# Placa_ATMEL_2019_v2.net
KiCad netlist of a schematic drawn in EAGLE
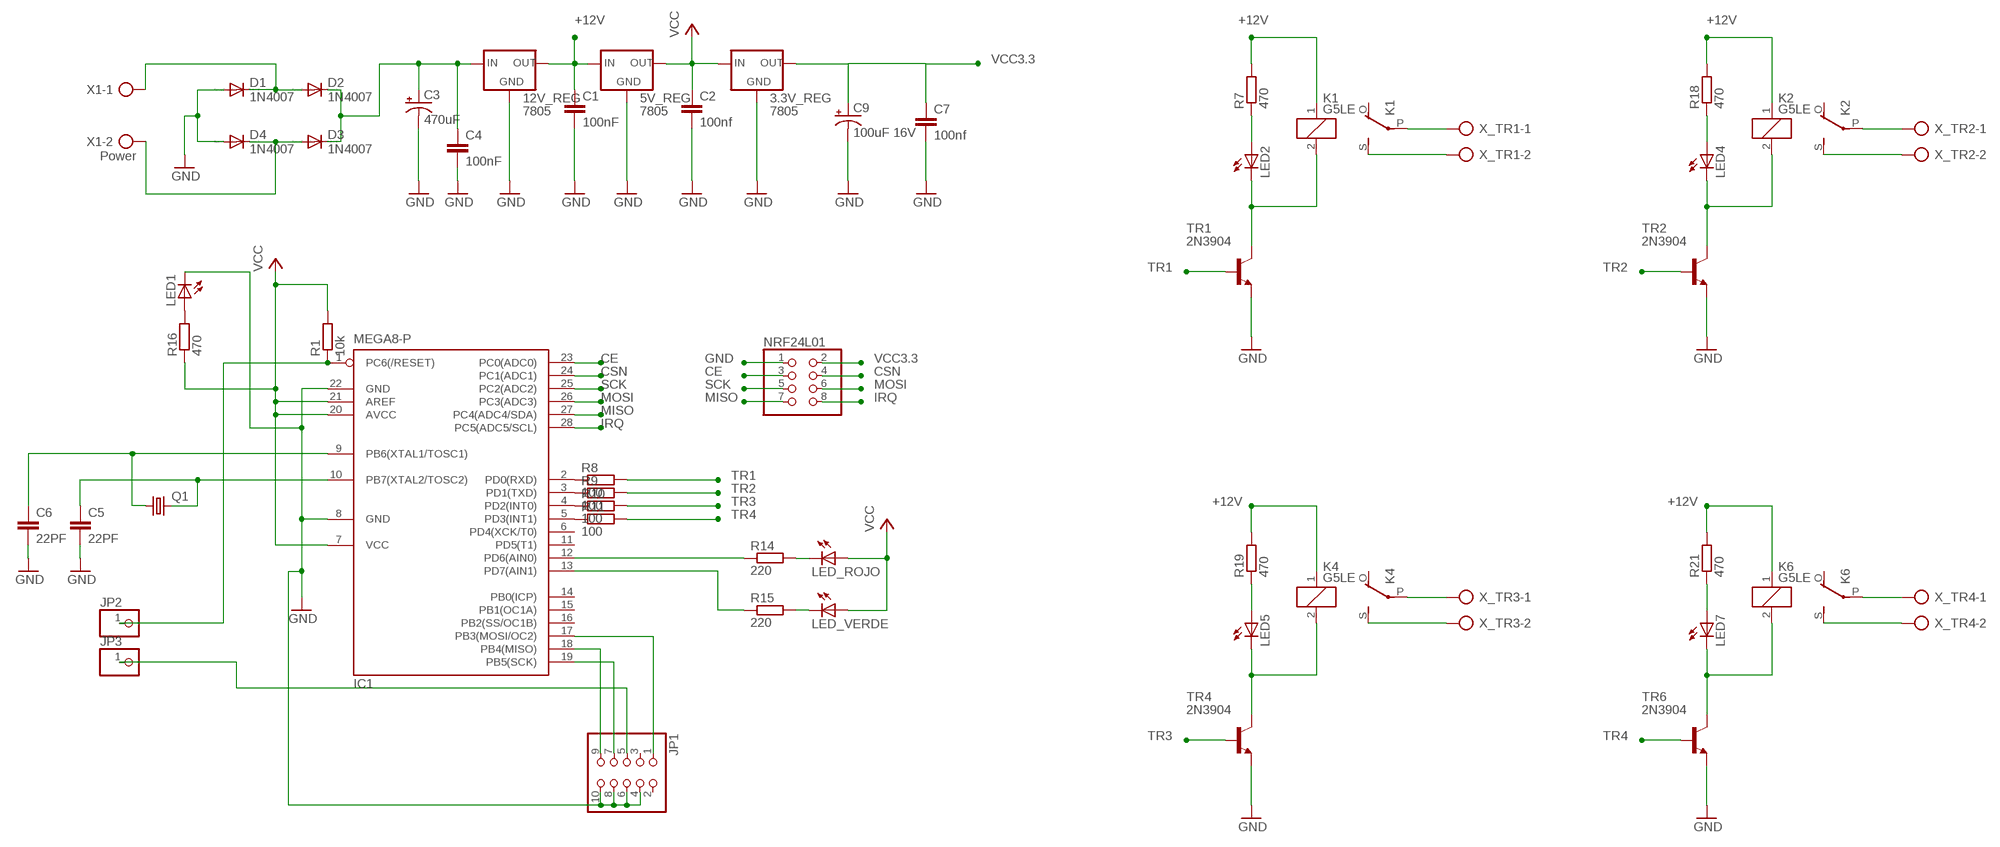
[diagram p0: schematic, sheet 1]

(export (version "E")
  (design (tool "Eeschema 10.0.6"))
  (components
    (comp (ref "3.3V_REG")
      (value "7805")
      (footprint "eagle-import:78XXL")
      (libsource (lib "eagle-import") (part "78XXL"))
    )
    (comp (ref "5V_REG")
      (value "7805")
      (footprint "eagle-import:78XXL")
      (libsource (lib "eagle-import") (part "78XXL"))
    )
    (comp (ref "12V_REG")
      (value "7805")
      (footprint "eagle-import:78XXL")
      (libsource (lib "eagle-import") (part "78XXL"))
    )
    (comp (ref "C1")
      (value "100nF")
      (footprint "eagle-import:C050-025X075")
      (libsource (lib "eagle-import") (part "C-EU050-025X075"))
    )
    (comp (ref "C2")
      (value "100nf")
      (footprint "eagle-import:C050-025X075")
      (libsource (lib "eagle-import") (part "C-EU050-025X075"))
    )
    (comp (ref "C3")
      (value "470uF")
      (footprint "eagle-import:E7,5-16")
      (libsource (lib "eagle-import") (part "CPOL-USE7.5-16"))
    )
    (comp (ref "C4")
      (value "100nF")
      (footprint "eagle-import:C050-025X075")
      (libsource (lib "eagle-import") (part "C-EU050-025X075"))
    )
    (comp (ref "C5")
      (value "22PF")
      (footprint "eagle-import:C050-024X044")
      (libsource (lib "eagle-import") (part "C-EU050-024X044"))
    )
    (comp (ref "C6")
      (value "22PF")
      (footprint "eagle-import:C050-024X044")
      (libsource (lib "eagle-import") (part "C-EU050-024X044"))
    )
    (comp (ref "C7")
      (value "100nf")
      (footprint "eagle-import:C050-025X075")
      (libsource (lib "eagle-import") (part "C-EU050-025X075"))
    )
    (comp (ref "C9")
      (value "100uF 16V")
      (footprint "eagle-import:E2,5-7")
      (libsource (lib "eagle-import") (part "CPOL-USE2.5-7"))
    )
    (comp (ref "D1")
      (value "1N4007")
      (footprint "eagle-import:DO41-10")
      (libsource (lib "eagle-import") (part "1N4004"))
    )
    (comp (ref "D2")
      (value "1N4007")
      (footprint "eagle-import:DO41-10")
      (libsource (lib "eagle-import") (part "1N4004"))
    )
    (comp (ref "D3")
      (value "1N4007")
      (footprint "eagle-import:DO41-10")
      (libsource (lib "eagle-import") (part "1N4004"))
    )
    (comp (ref "D4")
      (value "1N4007")
      (footprint "eagle-import:DO41-10")
      (libsource (lib "eagle-import") (part "1N4004"))
    )
    (comp (ref "IC1")
      (value "MEGA8-P")
      (footprint "eagle-import:DIL28-3")
      (libsource (lib "eagle-import") (part "MEGA8-P"))
    )
    (comp (ref "JP1")
      (value "PINHD-2X5")
      (footprint "eagle-import:2X05")
      (libsource (lib "eagle-import") (part "PINHD-2X5"))
    )
    (comp (ref "JP2")
      (value "PINHD-1X1")
      (footprint "eagle-import:1X01")
      (libsource (lib "eagle-import") (part "PINHD-1X1"))
    )
    (comp (ref "JP3")
      (value "PINHD-1X1")
      (footprint "eagle-import:1X01")
      (libsource (lib "eagle-import") (part "PINHD-1X1"))
    )
    (comp (ref "K1")
      (value "G5LE")
      (footprint "eagle-import:G5LE")
      (libsource (lib "eagle-import") (part "G5LE"))
    )
    (comp (ref "K2")
      (value "G5LE")
      (footprint "eagle-import:G5LE")
      (libsource (lib "eagle-import") (part "G5LE"))
    )
    (comp (ref "K4")
      (value "G5LE")
      (footprint "eagle-import:G5LE")
      (libsource (lib "eagle-import") (part "G5LE"))
    )
    (comp (ref "K6")
      (value "G5LE")
      (footprint "eagle-import:G5LE")
      (libsource (lib "eagle-import") (part "G5LE"))
    )
    (comp (ref "LED1")
      (value "LED5MM")
      (footprint "eagle-import:LED5MM")
      (libsource (lib "eagle-import") (part "LED5MM"))
    )
    (comp (ref "LED2")
      (value "LED5MM")
      (footprint "eagle-import:LED5MM")
      (libsource (lib "eagle-import") (part "LED5MM"))
    )
    (comp (ref "LED4")
      (value "LED5MM")
      (footprint "eagle-import:LED5MM")
      (libsource (lib "eagle-import") (part "LED5MM"))
    )
    (comp (ref "LED5")
      (value "LED5MM")
      (footprint "eagle-import:LED5MM")
      (libsource (lib "eagle-import") (part "LED5MM"))
    )
    (comp (ref "LED7")
      (value "LED5MM")
      (footprint "eagle-import:LED5MM")
      (libsource (lib "eagle-import") (part "LED5MM"))
    )
    (comp (ref "LED_ROJO")
      (value "LED5MM")
      (footprint "eagle-import:LED5MM")
      (libsource (lib "eagle-import") (part "LED5MM"))
    )
    (comp (ref "LED_VERDE")
      (value "LED5MM")
      (footprint "eagle-import:LED5MM")
      (libsource (lib "eagle-import") (part "LED5MM"))
    )
    (comp (ref "NRF24L01")
      (value "PINHD-2X4")
      (footprint "eagle-import:2X04")
      (libsource (lib "eagle-import") (part "PINHD-2X4"))
    )
    (comp (ref "Q1")
      (value "CRYSTALHC49S")
      (footprint "eagle-import:HC49_S")
      (libsource (lib "eagle-import") (part "CRYSTALHC49S"))
    )
    (comp (ref "R1")
      (value "10k")
      (footprint "eagle-import:0207_10")
      (libsource (lib "eagle-import") (part "R-EU_0207/10"))
    )
    (comp (ref "R7")
      (value "470")
      (footprint "eagle-import:0309_10")
      (libsource (lib "eagle-import") (part "R-EU_0309/10"))
    )
    (comp (ref "R8")
      (value "100")
      (footprint "eagle-import:0207_10")
      (libsource (lib "eagle-import") (part "R-EU_0207/10"))
    )
    (comp (ref "R9")
      (value "100")
      (footprint "eagle-import:0207_10")
      (libsource (lib "eagle-import") (part "R-EU_0207/10"))
    )
    (comp (ref "R10")
      (value "100")
      (footprint "eagle-import:0207_15")
      (libsource (lib "eagle-import") (part "R-EU_0207/15"))
    )
    (comp (ref "R11")
      (value "100")
      (footprint "eagle-import:0207_10")
      (libsource (lib "eagle-import") (part "R-EU_0207/10"))
    )
    (comp (ref "R14")
      (value "220")
      (footprint "eagle-import:0207_10")
      (libsource (lib "eagle-import") (part "R-EU_0207/10"))
    )
    (comp (ref "R15")
      (value "220")
      (footprint "eagle-import:0207_10")
      (libsource (lib "eagle-import") (part "R-EU_0207/10"))
    )
    (comp (ref "R16")
      (value "470")
      (footprint "eagle-import:0309_10")
      (libsource (lib "eagle-import") (part "R-EU_0309/10"))
    )
    (comp (ref "R18")
      (value "470")
      (footprint "eagle-import:0309_10")
      (libsource (lib "eagle-import") (part "R-EU_0309/10"))
    )
    (comp (ref "R19")
      (value "470")
      (footprint "eagle-import:0309_10")
      (libsource (lib "eagle-import") (part "R-EU_0309/10"))
    )
    (comp (ref "R21")
      (value "470")
      (footprint "eagle-import:0309_10")
      (libsource (lib "eagle-import") (part "R-EU_0309/10"))
    )
    (comp (ref "TR1")
      (value "2N3904")
      (footprint "eagle-import:TO92")
      (libsource (lib "eagle-import") (part "2N3904"))
    )
    (comp (ref "TR2")
      (value "2N3904")
      (footprint "eagle-import:TO92")
      (libsource (lib "eagle-import") (part "2N3904"))
    )
    (comp (ref "TR4")
      (value "2N3904")
      (footprint "eagle-import:TO92")
      (libsource (lib "eagle-import") (part "2N3904"))
    )
    (comp (ref "TR6")
      (value "2N3904")
      (footprint "eagle-import:TO92")
      (libsource (lib "eagle-import") (part "2N3904"))
    )
    (comp (ref "X1")
      (value "Power")
      (footprint "eagle-import:AK500_2")
      (libsource (lib "eagle-import") (part "AK500/2"))
    )
    (comp (ref "X_TR1")
      (value "AK300/2")
      (footprint "eagle-import:AK300_2")
      (libsource (lib "eagle-import") (part "AK300/2"))
    )
    (comp (ref "X_TR2")
      (value "AK300/2")
      (footprint "eagle-import:AK300_2")
      (libsource (lib "eagle-import") (part "AK300/2"))
    )
    (comp (ref "X_TR3")
      (value "AK300/2")
      (footprint "eagle-import:AK300_2")
      (libsource (lib "eagle-import") (part "AK300/2"))
    )
    (comp (ref "X_TR4")
      (value "AK300/2")
      (footprint "eagle-import:AK300_2")
      (libsource (lib "eagle-import") (part "AK300/2"))
    )
  )
  (nets
    (net (code "1") (name "/+12V") (class "Default")
      (node (ref "12V_REG") (pin "OUT") (pinfunction "OUT_OUT") (pintype "passive"))
      (node (ref "5V_REG") (pin "IN") (pinfunction "IN_IN") (pintype "input"))
      (node (ref "C1") (pin "1") (pinfunction "1_1") (pintype "passive"))
      (node (ref "K1") (pin "1") (pinfunction "1_1") (pintype "passive"))
      (node (ref "K2") (pin "1") (pinfunction "1_1") (pintype "passive"))
      (node (ref "K4") (pin "1") (pinfunction "1_1") (pintype "passive"))
      (node (ref "K6") (pin "1") (pinfunction "1_1") (pintype "passive"))
      (node (ref "R18") (pin "2") (pinfunction "2_2") (pintype "passive"))
      (node (ref "R19") (pin "2") (pinfunction "2_2") (pintype "passive"))
      (node (ref "R21") (pin "2") (pinfunction "2_2") (pintype "passive"))
      (node (ref "R7") (pin "2") (pinfunction "2_2") (pintype "passive"))
    )
    (net (code "2") (name "/CE") (class "Default")
      (node (ref "IC1") (pin "23") (pinfunction "PC0(ADC0)_23") (pintype "bidirectional"))
      (node (ref "NRF24L01") (pin "3") (pinfunction "3_3") (pintype "passive"))
    )
    (net (code "3") (name "/CSN") (class "Default")
      (node (ref "IC1") (pin "24") (pinfunction "PC1(ADC1)_24") (pintype "bidirectional"))
      (node (ref "NRF24L01") (pin "4") (pinfunction "4_4") (pintype "passive"))
    )
    (net (code "4") (name "/IRQ") (class "Default")
      (node (ref "IC1") (pin "28") (pinfunction "PC5(ADC5/SCL)_28") (pintype "bidirectional"))
      (node (ref "NRF24L01") (pin "8") (pinfunction "8_8") (pintype "passive"))
    )
    (net (code "5") (name "/MISO") (class "Default")
      (node (ref "IC1") (pin "27") (pinfunction "PC4(ADC4/SDA)_27") (pintype "bidirectional"))
      (node (ref "NRF24L01") (pin "7") (pinfunction "7_7") (pintype "passive"))
    )
    (net (code "6") (name "/MOSI") (class "Default")
      (node (ref "IC1") (pin "26") (pinfunction "PC3(ADC3)_26") (pintype "bidirectional"))
      (node (ref "NRF24L01") (pin "6") (pinfunction "6_6") (pintype "passive"))
    )
    (net (code "7") (name "/SCK") (class "Default")
      (node (ref "IC1") (pin "25") (pinfunction "PC2(ADC2)_25") (pintype "bidirectional"))
      (node (ref "NRF24L01") (pin "5") (pinfunction "5_5") (pintype "passive"))
    )
    (net (code "8") (name "/TR1") (class "Default")
      (node (ref "R8") (pin "2") (pinfunction "2_2") (pintype "passive"))
      (node (ref "TR1") (pin "2") (pinfunction "B_2") (pintype "passive"))
    )
    (net (code "9") (name "/TR2") (class "Default")
      (node (ref "R9") (pin "2") (pinfunction "2_2") (pintype "passive"))
      (node (ref "TR2") (pin "2") (pinfunction "B_2") (pintype "passive"))
    )
    (net (code "10") (name "/TR3") (class "Default")
      (node (ref "R10") (pin "2") (pinfunction "2_2") (pintype "passive"))
      (node (ref "TR4") (pin "2") (pinfunction "B_2") (pintype "passive"))
    )
    (net (code "11") (name "/TR4") (class "Default")
      (node (ref "R11") (pin "2") (pinfunction "2_2") (pintype "passive"))
      (node (ref "TR6") (pin "2") (pinfunction "B_2") (pintype "passive"))
    )
    (net (code "12") (name "/VCC3.3") (class "Default")
      (node (ref "3.3V_REG") (pin "OUT") (pinfunction "OUT_OUT") (pintype "passive"))
      (node (ref "C7") (pin "1") (pinfunction "1_1") (pintype "passive"))
      (node (ref "C9") (pin "+") (pinfunction "+_+") (pintype "passive"))
      (node (ref "NRF24L01") (pin "2") (pinfunction "2_2") (pintype "passive"))
    )
    (net (code "13") (name "GND") (class "Default")
      (node (ref "12V_REG") (pin "GND") (pinfunction "GND_GND") (pintype "input"))
      (node (ref "3.3V_REG") (pin "GND") (pinfunction "GND_GND") (pintype "input"))
      (node (ref "5V_REG") (pin "GND") (pinfunction "GND_GND") (pintype "input"))
      (node (ref "C1") (pin "2") (pinfunction "2_2") (pintype "passive"))
      (node (ref "C2") (pin "2") (pinfunction "2_2") (pintype "passive"))
      (node (ref "C3") (pin "-") (pinfunction "-_-") (pintype "passive"))
      (node (ref "C4") (pin "2") (pinfunction "2_2") (pintype "passive"))
      (node (ref "C5") (pin "2") (pinfunction "2_2") (pintype "passive"))
      (node (ref "C6") (pin "2") (pinfunction "2_2") (pintype "passive"))
      (node (ref "C7") (pin "2") (pinfunction "2_2") (pintype "passive"))
      (node (ref "C9") (pin "-") (pinfunction "-_-") (pintype "passive"))
      (node (ref "D1") (pin "A") (pinfunction "A_A") (pintype "passive"))
      (node (ref "D4") (pin "A") (pinfunction "A_A") (pintype "passive"))
      (node (ref "IC1") (pin "22") (pinfunction "GND_22") (pintype "power_in"))
      (node (ref "IC1") (pin "8") (pinfunction "GND_8") (pintype "power_in"))
      (node (ref "JP1") (pin "10") (pinfunction "10_10") (pintype "passive"))
      (node (ref "JP1") (pin "4") (pinfunction "4_4") (pintype "passive"))
      (node (ref "JP1") (pin "6") (pinfunction "6_6") (pintype "passive"))
      (node (ref "JP1") (pin "8") (pinfunction "8_8") (pintype "passive"))
      (node (ref "LED1") (pin "K") (pinfunction "C_K") (pintype "passive"))
      (node (ref "NRF24L01") (pin "1") (pinfunction "1_1") (pintype "passive"))
      (node (ref "TR1") (pin "3") (pinfunction "E_3") (pintype "passive"))
      (node (ref "TR2") (pin "3") (pinfunction "E_3") (pintype "passive"))
      (node (ref "TR4") (pin "3") (pinfunction "E_3") (pintype "passive"))
      (node (ref "TR6") (pin "3") (pinfunction "E_3") (pintype "passive"))
    )
    (net (code "14") (name "Net-(12V_REG-PadIN)") (class "Default")
      (node (ref "12V_REG") (pin "IN") (pinfunction "IN_IN") (pintype "input"))
      (node (ref "C3") (pin "+") (pinfunction "+_+") (pintype "passive"))
      (node (ref "C4") (pin "1") (pinfunction "1_1") (pintype "passive"))
      (node (ref "D2") (pin "C") (pinfunction "C_C") (pintype "passive"))
      (node (ref "D3") (pin "C") (pinfunction "C_C") (pintype "passive"))
    )
    (net (code "15") (name "Net-(IC1-PB3(MOSI{slash}OC2))") (class "Default")
      (node (ref "IC1") (pin "17") (pinfunction "PB3(MOSI/OC2)_17") (pintype "bidirectional"))
      (node (ref "JP1") (pin "1") (pinfunction "1_1") (pintype "passive"))
    )
    (net (code "16") (name "Net-(IC1-PB4(MISO))") (class "Default")
      (node (ref "IC1") (pin "18") (pinfunction "PB4(MISO)_18") (pintype "bidirectional"))
      (node (ref "JP1") (pin "9") (pinfunction "9_9") (pintype "passive"))
    )
    (net (code "17") (name "Net-(IC1-PB5(SCK))") (class "Default")
      (node (ref "IC1") (pin "19") (pinfunction "PB5(SCK)_19") (pintype "bidirectional"))
      (node (ref "JP1") (pin "7") (pinfunction "7_7") (pintype "passive"))
    )
    (net (code "18") (name "Net-(IC1-PB6(XTAL1{slash}TOSC1))") (class "Default")
      (node (ref "C6") (pin "1") (pinfunction "1_1") (pintype "passive"))
      (node (ref "IC1") (pin "9") (pinfunction "PB6(XTAL1/TOSC1)_9") (pintype "bidirectional"))
      (node (ref "Q1") (pin "1") (pinfunction "1_1") (pintype "passive"))
    )
    (net (code "19") (name "Net-(IC1-PB7(XTAL2{slash}TOSC2))") (class "Default")
      (node (ref "C5") (pin "1") (pinfunction "1_1") (pintype "passive"))
      (node (ref "IC1") (pin "10") (pinfunction "PB7(XTAL2/TOSC2)_10") (pintype "bidirectional"))
      (node (ref "Q1") (pin "2") (pinfunction "2_2") (pintype "passive"))
    )
    (net (code "20") (name "Net-(IC1-PC6({slash}RESET))") (class "Default")
      (node (ref "IC1") (pin "1") (pinfunction "PC6(/RESET)_1") (pintype "bidirectional"))
      (node (ref "JP2") (pin "1") (pinfunction "1_1") (pintype "passive"))
      (node (ref "R1") (pin "1") (pinfunction "1_1") (pintype "passive"))
    )
    (net (code "21") (name "Net-(IC1-PD0(RXD))") (class "Default")
      (node (ref "IC1") (pin "2") (pinfunction "PD0(RXD)_2") (pintype "bidirectional"))
      (node (ref "R8") (pin "1") (pinfunction "1_1") (pintype "passive"))
    )
    (net (code "22") (name "Net-(IC1-PD1(TXD))") (class "Default")
      (node (ref "IC1") (pin "3") (pinfunction "PD1(TXD)_3") (pintype "bidirectional"))
      (node (ref "R9") (pin "1") (pinfunction "1_1") (pintype "passive"))
    )
    (net (code "23") (name "Net-(IC1-PD2(INT0))") (class "Default")
      (node (ref "IC1") (pin "4") (pinfunction "PD2(INT0)_4") (pintype "bidirectional"))
      (node (ref "R10") (pin "1") (pinfunction "1_1") (pintype "passive"))
    )
    (net (code "24") (name "Net-(IC1-PD3(INT1))") (class "Default")
      (node (ref "IC1") (pin "5") (pinfunction "PD3(INT1)_5") (pintype "bidirectional"))
      (node (ref "R11") (pin "1") (pinfunction "1_1") (pintype "passive"))
    )
    (net (code "25") (name "Net-(IC1-PD6(AIN0))") (class "Default")
      (node (ref "IC1") (pin "12") (pinfunction "PD6(AIN0)_12") (pintype "bidirectional"))
      (node (ref "R14") (pin "1") (pinfunction "1_1") (pintype "passive"))
    )
    (net (code "26") (name "Net-(IC1-PD7(AIN1))") (class "Default")
      (node (ref "IC1") (pin "13") (pinfunction "PD7(AIN1)_13") (pintype "bidirectional"))
      (node (ref "R15") (pin "1") (pinfunction "1_1") (pintype "passive"))
    )
    (net (code "27") (name "Net-(JP1-Pad5)") (class "Default")
      (node (ref "JP1") (pin "5") (pinfunction "5_5") (pintype "passive"))
      (node (ref "JP3") (pin "1") (pinfunction "1_1") (pintype "passive"))
    )
    (net (code "28") (name "Net-(LED1-PadA)") (class "Default")
      (node (ref "LED1") (pin "A") (pinfunction "A_A") (pintype "passive"))
      (node (ref "R16") (pin "2") (pinfunction "2_2") (pintype "passive"))
    )
    (net (code "29") (name "Net-(LED2-C)") (class "Default")
      (node (ref "K1") (pin "2") (pinfunction "2_2") (pintype "passive"))
      (node (ref "LED2") (pin "K") (pinfunction "C_K") (pintype "passive"))
      (node (ref "TR1") (pin "1") (pinfunction "C_1") (pintype "passive"))
    )
    (net (code "30") (name "Net-(LED2-PadA)") (class "Default")
      (node (ref "LED2") (pin "A") (pinfunction "A_A") (pintype "passive"))
      (node (ref "R7") (pin "1") (pinfunction "1_1") (pintype "passive"))
    )
    (net (code "31") (name "Net-(LED4-C)") (class "Default")
      (node (ref "K2") (pin "2") (pinfunction "2_2") (pintype "passive"))
      (node (ref "LED4") (pin "K") (pinfunction "C_K") (pintype "passive"))
      (node (ref "TR2") (pin "1") (pinfunction "C_1") (pintype "passive"))
    )
    (net (code "32") (name "Net-(LED4-PadA)") (class "Default")
      (node (ref "LED4") (pin "A") (pinfunction "A_A") (pintype "passive"))
      (node (ref "R18") (pin "1") (pinfunction "1_1") (pintype "passive"))
    )
    (net (code "33") (name "Net-(LED5-C)") (class "Default")
      (node (ref "K4") (pin "2") (pinfunction "2_2") (pintype "passive"))
      (node (ref "LED5") (pin "K") (pinfunction "C_K") (pintype "passive"))
      (node (ref "TR4") (pin "1") (pinfunction "C_1") (pintype "passive"))
    )
    (net (code "34") (name "Net-(LED5-PadA)") (class "Default")
      (node (ref "LED5") (pin "A") (pinfunction "A_A") (pintype "passive"))
      (node (ref "R19") (pin "1") (pinfunction "1_1") (pintype "passive"))
    )
    (net (code "35") (name "Net-(LED7-C)") (class "Default")
      (node (ref "K6") (pin "2") (pinfunction "2_2") (pintype "passive"))
      (node (ref "LED7") (pin "K") (pinfunction "C_K") (pintype "passive"))
      (node (ref "TR6") (pin "1") (pinfunction "C_1") (pintype "passive"))
    )
    (net (code "36") (name "Net-(LED7-PadA)") (class "Default")
      (node (ref "LED7") (pin "A") (pinfunction "A_A") (pintype "passive"))
      (node (ref "R21") (pin "1") (pinfunction "1_1") (pintype "passive"))
    )
    (net (code "37") (name "Net-(LED_ROJO-C)") (class "Default")
      (node (ref "LED_ROJO") (pin "K") (pinfunction "C_K") (pintype "passive"))
      (node (ref "R14") (pin "2") (pinfunction "2_2") (pintype "passive"))
    )
    (net (code "38") (name "Net-(LED_VERDE-C)") (class "Default")
      (node (ref "LED_VERDE") (pin "K") (pinfunction "C_K") (pintype "passive"))
      (node (ref "R15") (pin "2") (pinfunction "2_2") (pintype "passive"))
    )
    (net (code "39") (name "Net-(X1A-KL)") (class "Default")
      (node (ref "D1") (pin "C") (pinfunction "C_C") (pintype "passive"))
      (node (ref "D2") (pin "A") (pinfunction "A_A") (pintype "passive"))
      (node (ref "X1") (pin "1") (pinfunction "KL_1") (pintype "passive"))
    )
    (net (code "40") (name "Net-(X1B-KL)") (class "Default")
      (node (ref "D3") (pin "A") (pinfunction "A_A") (pintype "passive"))
      (node (ref "D4") (pin "C") (pinfunction "C_C") (pintype "passive"))
      (node (ref "X1") (pin "2") (pinfunction "KL_2") (pintype "passive"))
    )
    (net (code "41") (name "Net-(X_TR1A-KL)") (class "Default")
      (node (ref "K1") (pin "P") (pinfunction "P_P") (pintype "passive"))
      (node (ref "X_TR1") (pin "1") (pinfunction "KL_1") (pintype "passive"))
    )
    (net (code "42") (name "Net-(X_TR1B-KL)") (class "Default")
      (node (ref "K1") (pin "S") (pinfunction "S_S") (pintype "passive"))
      (node (ref "X_TR1") (pin "2") (pinfunction "KL_2") (pintype "passive"))
    )
    (net (code "43") (name "Net-(X_TR2A-KL)") (class "Default")
      (node (ref "K2") (pin "P") (pinfunction "P_P") (pintype "passive"))
      (node (ref "X_TR2") (pin "1") (pinfunction "KL_1") (pintype "passive"))
    )
    (net (code "44") (name "Net-(X_TR2B-KL)") (class "Default")
      (node (ref "K2") (pin "S") (pinfunction "S_S") (pintype "passive"))
      (node (ref "X_TR2") (pin "2") (pinfunction "KL_2") (pintype "passive"))
    )
    (net (code "45") (name "Net-(X_TR3A-KL)") (class "Default")
      (node (ref "K4") (pin "P") (pinfunction "P_P") (pintype "passive"))
      (node (ref "X_TR3") (pin "1") (pinfunction "KL_1") (pintype "passive"))
    )
    (net (code "46") (name "Net-(X_TR3B-KL)") (class "Default")
      (node (ref "K4") (pin "S") (pinfunction "S_S") (pintype "passive"))
      (node (ref "X_TR3") (pin "2") (pinfunction "KL_2") (pintype "passive"))
    )
    (net (code "47") (name "Net-(X_TR4A-KL)") (class "Default")
      (node (ref "K6") (pin "P") (pinfunction "P_P") (pintype "passive"))
      (node (ref "X_TR4") (pin "1") (pinfunction "KL_1") (pintype "passive"))
    )
    (net (code "48") (name "Net-(X_TR4B-KL)") (class "Default")
      (node (ref "K6") (pin "S") (pinfunction "S_S") (pintype "passive"))
      (node (ref "X_TR4") (pin "2") (pinfunction "KL_2") (pintype "passive"))
    )
    (net (code "49") (name "VCC") (class "Default")
      (node (ref "3.3V_REG") (pin "IN") (pinfunction "IN_IN") (pintype "input"))
      (node (ref "5V_REG") (pin "OUT") (pinfunction "OUT_OUT") (pintype "passive"))
      (node (ref "C2") (pin "1") (pinfunction "1_1") (pintype "passive"))
      (node (ref "IC1") (pin "20") (pinfunction "AVCC_20") (pintype "power_in"))
      (node (ref "IC1") (pin "21") (pinfunction "AREF_21") (pintype "passive"))
      (node (ref "IC1") (pin "7") (pinfunction "VCC_7") (pintype "power_in"))
      (node (ref "LED_ROJO") (pin "A") (pinfunction "A_A") (pintype "passive"))
      (node (ref "LED_VERDE") (pin "A") (pinfunction "A_A") (pintype "passive"))
      (node (ref "R1") (pin "2") (pinfunction "2_2") (pintype "passive"))
      (node (ref "R16") (pin "1") (pinfunction "1_1") (pintype "passive"))
    )
    (net (code "50") (name "unconnected-(IC1-PB0(ICP)-Pad14)") (class "Default")
      (node (ref "IC1") (pin "14") (pinfunction "PB0(ICP)_14") (pintype "bidirectional"))
    )
    (net (code "51") (name "unconnected-(IC1-PB1(OC1A)-Pad15)") (class "Default")
      (node (ref "IC1") (pin "15") (pinfunction "PB1(OC1A)_15") (pintype "bidirectional"))
    )
    (net (code "52") (name "unconnected-(IC1-PB2(SS{slash}OC1B)-Pad16)") (class "Default")
      (node (ref "IC1") (pin "16") (pinfunction "PB2(SS/OC1B)_16") (pintype "bidirectional"))
    )
    (net (code "53") (name "unconnected-(IC1-PD4(XCK{slash}T0)-Pad6)") (class "Default")
      (node (ref "IC1") (pin "6") (pinfunction "PD4(XCK/T0)_6") (pintype "bidirectional"))
    )
    (net (code "54") (name "unconnected-(IC1-PD5(T1)-Pad11)") (class "Default")
      (node (ref "IC1") (pin "11") (pinfunction "PD5(T1)_11") (pintype "bidirectional"))
    )
    (net (code "55") (name "unconnected-(JP1-Pad2)") (class "Default")
      (node (ref "JP1") (pin "2") (pinfunction "2_2") (pintype "passive"))
    )
    (net (code "56") (name "unconnected-(JP1-Pad3)") (class "Default")
      (node (ref "JP1") (pin "3") (pinfunction "3_3") (pintype "passive"))
    )
    (net (code "57") (name "unconnected-(K1-PadO)") (class "Default")
      (node (ref "K1") (pin "O") (pinfunction "O_O") (pintype "passive"))
    )
    (net (code "58") (name "unconnected-(K2-PadO)") (class "Default")
      (node (ref "K2") (pin "O") (pinfunction "O_O") (pintype "passive"))
    )
    (net (code "59") (name "unconnected-(K4-PadO)") (class "Default")
      (node (ref "K4") (pin "O") (pinfunction "O_O") (pintype "passive"))
    )
    (net (code "60") (name "unconnected-(K6-PadO)") (class "Default")
      (node (ref "K6") (pin "O") (pinfunction "O_O") (pintype "passive"))
    )
  )
)
